# PCB_Breakout.net
KiCad netlist of a schematic drawn in EAGLE
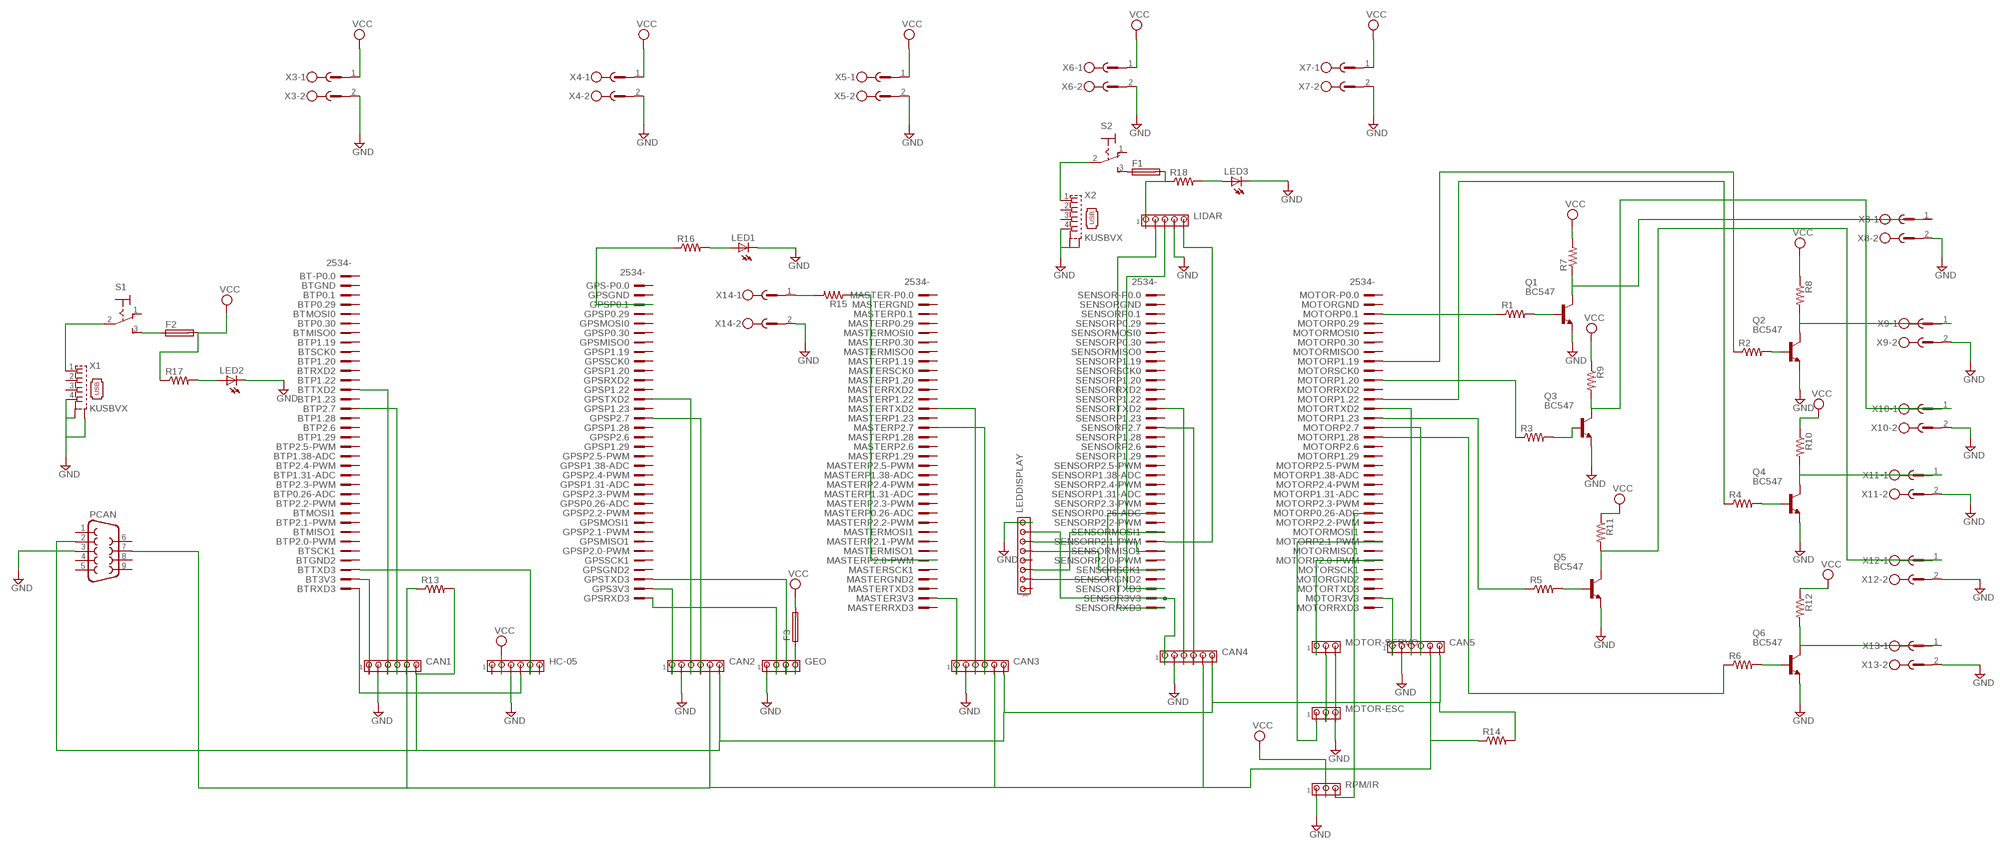
[diagram p0: schematic, sheet 1]

(export (version "E")
  (design (tool "Eeschema 10.0.6"))
  (components
    (comp (ref "BT")
      (value "2534-")
      (footprint "eagle-import:PAK100_2500-34")
      (libsource (lib "eagle-import") (part "2534-"))
    )
    (comp (ref "CAN1")
      (value "MTA06-100")
      (footprint "eagle-import:10X06MTA")
      (libsource (lib "eagle-import") (part "MTA06-100"))
    )
    (comp (ref "CAN2")
      (value "MTA06-100")
      (footprint "eagle-import:10X06MTA")
      (libsource (lib "eagle-import") (part "MTA06-100"))
    )
    (comp (ref "CAN3")
      (value "MTA06-100")
      (footprint "eagle-import:10X06MTA")
      (libsource (lib "eagle-import") (part "MTA06-100"))
    )
    (comp (ref "CAN4")
      (value "MTA06-100")
      (footprint "eagle-import:10X06MTA")
      (libsource (lib "eagle-import") (part "MTA06-100"))
    )
    (comp (ref "CAN5")
      (value "MTA06-100")
      (footprint "eagle-import:10X06MTA")
      (libsource (lib "eagle-import") (part "MTA06-100"))
    )
    (comp (ref "F1")
      (value "SH22,5")
      (footprint "eagle-import:SH22,5")
      (fields (field (name "MF") "SCHURTER") (field (name "MPN") "0031.8201"))
      (libsource (lib "eagle-import") (part "SH22,5"))
    )
    (comp (ref "F2")
      (value "SH22,5")
      (footprint "eagle-import:SH22,5")
      (fields (field (name "MF") "SCHURTER") (field (name "MPN") "0031.8201"))
      (libsource (lib "eagle-import") (part "SH22,5"))
    )
    (comp (ref "F3")
      (value "SH22,5")
      (footprint "eagle-import:SH22,5")
      (fields (field (name "MF") "SCHURTER") (field (name "MPN") "0031.8201"))
      (libsource (lib "eagle-import") (part "SH22,5"))
    )
    (comp (ref "GEO")
      (value "MTA04-100")
      (footprint "eagle-import:10X04MTA")
      (libsource (lib "eagle-import") (part "MTA04-100"))
    )
    (comp (ref "GPS")
      (value "2534-")
      (footprint "eagle-import:PAK100_2500-34")
      (libsource (lib "eagle-import") (part "2534-"))
    )
    (comp (ref "HC-05")
      (value "MTA06-100")
      (footprint "eagle-import:10X06MTA")
      (libsource (lib "eagle-import") (part "MTA06-100"))
    )
    (comp (ref "LED1")
      (value "LED5MM")
      (footprint "eagle-import:LED5MM")
      (libsource (lib "eagle-import") (part "LED5MM"))
    )
    (comp (ref "LED2")
      (value "LED5MM")
      (footprint "eagle-import:LED5MM")
      (libsource (lib "eagle-import") (part "LED5MM"))
    )
    (comp (ref "LED3")
      (value "LED5MM")
      (footprint "eagle-import:LED5MM")
      (libsource (lib "eagle-import") (part "LED5MM"))
    )
    (comp (ref "LEDDISPLAY")
      (value "MTA08-100")
      (footprint "eagle-import:10X08MTA")
      (libsource (lib "eagle-import") (part "MTA08-100"))
    )
    (comp (ref "LIDAR")
      (value "MTA05-100")
      (footprint "eagle-import:10X05MTA")
      (libsource (lib "eagle-import") (part "MTA05-100"))
    )
    (comp (ref "MASTER")
      (value "2534-")
      (footprint "eagle-import:PAK100_2500-34")
      (libsource (lib "eagle-import") (part "2534-"))
    )
    (comp (ref "MOTOR")
      (value "2534-")
      (footprint "eagle-import:PAK100_2500-34")
      (libsource (lib "eagle-import") (part "2534-"))
    )
    (comp (ref "MOTOR-ESC")
      (value "MTA03-100")
      (footprint "eagle-import:10X03MTA")
      (libsource (lib "eagle-import") (part "MTA03-100"))
    )
    (comp (ref "MOTOR-SERVO")
      (value "MTA03-100")
      (footprint "eagle-import:10X03MTA")
      (libsource (lib "eagle-import") (part "MTA03-100"))
    )
    (comp (ref "PCAN")
      (value "F09HP")
      (footprint "eagle-import:F09HP")
      (libsource (lib "eagle-import") (part "F09HP"))
    )
    (comp (ref "Q1")
      (value "BC547")
      (footprint "eagle-import:TO92")
      (libsource (lib "eagle-import") (part "BC547"))
    )
    (comp (ref "Q2")
      (value "BC547")
      (footprint "eagle-import:TO92")
      (libsource (lib "eagle-import") (part "BC547"))
    )
    (comp (ref "Q3")
      (value "BC547")
      (footprint "eagle-import:TO92")
      (libsource (lib "eagle-import") (part "BC547"))
    )
    (comp (ref "Q4")
      (value "BC547")
      (footprint "eagle-import:TO92")
      (libsource (lib "eagle-import") (part "BC547"))
    )
    (comp (ref "Q5")
      (value "BC547")
      (footprint "eagle-import:TO92")
      (libsource (lib "eagle-import") (part "BC547"))
    )
    (comp (ref "Q6")
      (value "BC547")
      (footprint "eagle-import:TO92")
      (libsource (lib "eagle-import") (part "BC547"))
    )
    (comp (ref "R1")
      (value "R-US_0207/10")
      (footprint "eagle-import:0207_10")
      (libsource (lib "eagle-import") (part "R-US_0207/10"))
    )
    (comp (ref "R2")
      (value "R-US_0207/10")
      (footprint "eagle-import:0207_10")
      (libsource (lib "eagle-import") (part "R-US_0207/10"))
    )
    (comp (ref "R3")
      (value "R-US_0207/10")
      (footprint "eagle-import:0207_10")
      (libsource (lib "eagle-import") (part "R-US_0207/10"))
    )
    (comp (ref "R4")
      (value "R-US_0207/10")
      (footprint "eagle-import:0207_10")
      (libsource (lib "eagle-import") (part "R-US_0207/10"))
    )
    (comp (ref "R5")
      (value "R-US_0207/10")
      (footprint "eagle-import:0207_10")
      (libsource (lib "eagle-import") (part "R-US_0207/10"))
    )
    (comp (ref "R6")
      (value "R-US_0207/10")
      (footprint "eagle-import:0207_10")
      (libsource (lib "eagle-import") (part "R-US_0207/10"))
    )
    (comp (ref "R7")
      (value "R-US_0207/10")
      (footprint "eagle-import:0207_10")
      (libsource (lib "eagle-import") (part "R-US_0207/10"))
    )
    (comp (ref "R8")
      (value "R-US_0207/10")
      (footprint "eagle-import:0207_10")
      (libsource (lib "eagle-import") (part "R-US_0207/10"))
    )
    (comp (ref "R9")
      (value "R-US_0207/10")
      (footprint "eagle-import:0207_10")
      (libsource (lib "eagle-import") (part "R-US_0207/10"))
    )
    (comp (ref "R10")
      (value "R-US_0207/10")
      (footprint "eagle-import:0207_10")
      (libsource (lib "eagle-import") (part "R-US_0207/10"))
    )
    (comp (ref "R11")
      (value "R-US_0207/10")
      (footprint "eagle-import:0207_10")
      (libsource (lib "eagle-import") (part "R-US_0207/10"))
    )
    (comp (ref "R12")
      (value "R-US_0207/10")
      (footprint "eagle-import:0207_10")
      (libsource (lib "eagle-import") (part "R-US_0207/10"))
    )
    (comp (ref "R13")
      (value "R-US_0207/10")
      (footprint "eagle-import:0207_10")
      (libsource (lib "eagle-import") (part "R-US_0207/10"))
    )
    (comp (ref "R14")
      (value "R-US_0207/10")
      (footprint "eagle-import:0207_10")
      (libsource (lib "eagle-import") (part "R-US_0207/10"))
    )
    (comp (ref "R15")
      (value "R-US_0207/10")
      (footprint "eagle-import:0207_10")
      (libsource (lib "eagle-import") (part "R-US_0207/10"))
    )
    (comp (ref "R16")
      (value "R-US_0207/10")
      (footprint "eagle-import:0207_10")
      (libsource (lib "eagle-import") (part "R-US_0207/10"))
    )
    (comp (ref "R17")
      (value "R-US_0207/10")
      (footprint "eagle-import:0207_10")
      (libsource (lib "eagle-import") (part "R-US_0207/10"))
    )
    (comp (ref "R18")
      (value "R-US_0207/10")
      (footprint "eagle-import:0207_10")
      (libsource (lib "eagle-import") (part "R-US_0207/10"))
    )
    (comp (ref "RPM/IR")
      (value "MTA03-100")
      (footprint "eagle-import:10X03MTA")
      (libsource (lib "eagle-import") (part "MTA03-100"))
    )
    (comp (ref "S1")
      (value "M9040P")
      (footprint "eagle-import:M9040P")
      (libsource (lib "eagle-import") (part "M9040P"))
    )
    (comp (ref "S2")
      (value "M9040P")
      (footprint "eagle-import:M9040P")
      (libsource (lib "eagle-import") (part "M9040P"))
    )
    (comp (ref "SENSOR")
      (value "2534-")
      (footprint "eagle-import:PAK100_2500-34")
      (libsource (lib "eagle-import") (part "2534-"))
    )
    (comp (ref "X1")
      (value "KUSBVX")
      (footprint "eagle-import:KUSBVX")
      (libsource (lib "eagle-import") (part "KUSBVX"))
    )
    (comp (ref "X2")
      (value "KUSBVX")
      (footprint "eagle-import:KUSBVX")
      (libsource (lib "eagle-import") (part "KUSBVX"))
    )
    (comp (ref "X3")
      (value "MSTBV2")
      (footprint "eagle-import:MSTBV2")
      (libsource (lib "eagle-import") (part "MSTBV2"))
    )
    (comp (ref "X4")
      (value "MSTBV2")
      (footprint "eagle-import:MSTBV2")
      (libsource (lib "eagle-import") (part "MSTBV2"))
    )
    (comp (ref "X5")
      (value "MSTBV2")
      (footprint "eagle-import:MSTBV2")
      (libsource (lib "eagle-import") (part "MSTBV2"))
    )
    (comp (ref "X6")
      (value "MSTBV2")
      (footprint "eagle-import:MSTBV2")
      (libsource (lib "eagle-import") (part "MSTBV2"))
    )
    (comp (ref "X7")
      (value "MSTBV2")
      (footprint "eagle-import:MSTBV2")
      (libsource (lib "eagle-import") (part "MSTBV2"))
    )
    (comp (ref "X8")
      (value "MSTBV2")
      (footprint "eagle-import:MSTBV2")
      (libsource (lib "eagle-import") (part "MSTBV2"))
    )
    (comp (ref "X9")
      (value "MSTBV2")
      (footprint "eagle-import:MSTBV2")
      (libsource (lib "eagle-import") (part "MSTBV2"))
    )
    (comp (ref "X10")
      (value "MSTBV2")
      (footprint "eagle-import:MSTBV2")
      (libsource (lib "eagle-import") (part "MSTBV2"))
    )
    (comp (ref "X11")
      (value "MSTBV2")
      (footprint "eagle-import:MSTBV2")
      (libsource (lib "eagle-import") (part "MSTBV2"))
    )
    (comp (ref "X12")
      (value "MSTBV2")
      (footprint "eagle-import:MSTBV2")
      (libsource (lib "eagle-import") (part "MSTBV2"))
    )
    (comp (ref "X13")
      (value "MSTBV2")
      (footprint "eagle-import:MSTBV2")
      (libsource (lib "eagle-import") (part "MSTBV2"))
    )
    (comp (ref "X14")
      (value "MSTBV2")
      (footprint "eagle-import:MSTBV2")
      (libsource (lib "eagle-import") (part "MSTBV2"))
    )
  )
  (nets
    (net (code "1") (name "GND") (class "Default")
      (node (ref "CAN1") (pin "5") (pinfunction "2_5") (pintype "passive"))
      (node (ref "CAN2") (pin "5") (pinfunction "2_5") (pintype "passive"))
      (node (ref "CAN3") (pin "5") (pinfunction "2_5") (pintype "passive"))
      (node (ref "CAN4") (pin "5") (pinfunction "2_5") (pintype "passive"))
      (node (ref "CAN5") (pin "5") (pinfunction "2_5") (pintype "passive"))
      (node (ref "GEO") (pin "1") (pinfunction "1_1") (pintype "passive"))
      (node (ref "HC-05") (pin "4") (pinfunction "3_4") (pintype "passive"))
      (node (ref "LED1") (pin "K") (pinfunction "C_K") (pintype "passive"))
      (node (ref "LED2") (pin "K") (pinfunction "C_K") (pintype "passive"))
      (node (ref "LED3") (pin "K") (pinfunction "C_K") (pintype "passive"))
      (node (ref "LEDDISPLAY") (pin "8") (pinfunction "8_8") (pintype "passive"))
      (node (ref "LIDAR") (pin "4") (pinfunction "4_4") (pintype "passive"))
      (node (ref "MOTOR-ESC") (pin "3") (pinfunction "3_3") (pintype "passive"))
      (node (ref "MOTOR-SERVO") (pin "3") (pinfunction "3_3") (pintype "passive"))
      (node (ref "PCAN") (pin "3") (pinfunction "3_3") (pintype "passive"))
      (node (ref "Q1") (pin "1") (pinfunction "E_1") (pintype "passive"))
      (node (ref "Q2") (pin "1") (pinfunction "E_1") (pintype "passive"))
      (node (ref "Q3") (pin "1") (pinfunction "E_1") (pintype "passive"))
      (node (ref "Q4") (pin "1") (pinfunction "E_1") (pintype "passive"))
      (node (ref "Q5") (pin "1") (pinfunction "E_1") (pintype "passive"))
      (node (ref "Q6") (pin "1") (pinfunction "E_1") (pintype "passive"))
      (node (ref "RPM/IR") (pin "1") (pinfunction "1_1") (pintype "passive"))
      (node (ref "X1") (pin "4") (pinfunction "4_4") (pintype "passive"))
      (node (ref "X1") (pin "M1") (pinfunction "S1_M1") (pintype "passive"))
      (node (ref "X1") (pin "M2") (pinfunction "S2_M2") (pintype "passive"))
      (node (ref "X10") (pin "2") (pinfunction "SK_2") (pintype "passive"))
      (node (ref "X11") (pin "2") (pinfunction "SK_2") (pintype "passive"))
      (node (ref "X12") (pin "2") (pinfunction "SK_2") (pintype "passive"))
      (node (ref "X13") (pin "2") (pinfunction "SK_2") (pintype "passive"))
      (node (ref "X14") (pin "2") (pinfunction "SK_2") (pintype "passive"))
      (node (ref "X2") (pin "4") (pinfunction "4_4") (pintype "passive"))
      (node (ref "X2") (pin "M1") (pinfunction "S1_M1") (pintype "passive"))
      (node (ref "X2") (pin "M2") (pinfunction "S2_M2") (pintype "passive"))
      (node (ref "X3") (pin "2") (pinfunction "SK_2") (pintype "passive"))
      (node (ref "X4") (pin "2") (pinfunction "SK_2") (pintype "passive"))
      (node (ref "X5") (pin "2") (pinfunction "SK_2") (pintype "passive"))
      (node (ref "X6") (pin "2") (pinfunction "SK_2") (pintype "passive"))
      (node (ref "X7") (pin "2") (pinfunction "SK_2") (pintype "passive"))
      (node (ref "X8") (pin "2") (pinfunction "SK_2") (pintype "passive"))
      (node (ref "X9") (pin "2") (pinfunction "SK_2") (pintype "passive"))
    )
    (net (code "2") (name "Net-(BTAB-KL)") (class "Default")
      (node (ref "BT") (pin "15") (pinfunction "KL_15") (pintype "passive"))
      (node (ref "CAN1") (pin "3") (pinfunction "4_3") (pintype "passive"))
    )
    (net (code "3") (name "Net-(BTAD-KL)") (class "Default")
      (node (ref "BT") (pin "34") (pinfunction "KL_34") (pintype "passive"))
      (node (ref "HC-05") (pin "3") (pinfunction "4_3") (pintype "passive"))
    )
    (net (code "4") (name "Net-(BTAG-KL)") (class "Default")
      (node (ref "BT") (pin "13") (pinfunction "KL_13") (pintype "passive"))
      (node (ref "CAN1") (pin "4") (pinfunction "3_4") (pintype "passive"))
    )
    (net (code "5") (name "Net-(BTAH-KL)") (class "Default")
      (node (ref "BT") (pin "32") (pinfunction "KL_32") (pintype "passive"))
      (node (ref "HC-05") (pin "2") (pinfunction "5_2") (pintype "passive"))
    )
    (net (code "6") (name "Net-(BTB-KL)") (class "Default")
      (node (ref "BT") (pin "33") (pinfunction "KL_33") (pintype "passive"))
      (node (ref "CAN1") (pin "6") (pinfunction "1_6") (pintype "passive"))
    )
    (net (code "7") (name "Net-(CAN1-5)") (class "Default")
      (node (ref "CAN1") (pin "2") (pinfunction "5_2") (pintype "passive"))
      (node (ref "CAN2") (pin "2") (pinfunction "5_2") (pintype "passive"))
      (node (ref "CAN3") (pin "2") (pinfunction "5_2") (pintype "passive"))
      (node (ref "CAN4") (pin "2") (pinfunction "5_2") (pintype "passive"))
      (node (ref "CAN5") (pin "2") (pinfunction "5_2") (pintype "passive"))
      (node (ref "PCAN") (pin "7") (pinfunction "7_7") (pintype "passive"))
      (node (ref "R13") (pin "1") (pinfunction "1_1") (pintype "passive"))
      (node (ref "R14") (pin "1") (pinfunction "1_1") (pintype "passive"))
    )
    (net (code "8") (name "Net-(CAN1-6)") (class "Default")
      (node (ref "CAN1") (pin "1") (pinfunction "6_1") (pintype "passive"))
      (node (ref "CAN2") (pin "1") (pinfunction "6_1") (pintype "passive"))
      (node (ref "CAN3") (pin "1") (pinfunction "6_1") (pintype "passive"))
      (node (ref "CAN4") (pin "1") (pinfunction "6_1") (pintype "passive"))
      (node (ref "CAN5") (pin "1") (pinfunction "6_1") (pintype "passive"))
      (node (ref "PCAN") (pin "2") (pinfunction "2_2") (pintype "passive"))
      (node (ref "R13") (pin "2") (pinfunction "2_2") (pintype "passive"))
      (node (ref "R14") (pin "2") (pinfunction "2_2") (pintype "passive"))
    )
    (net (code "9") (name "Net-(CAN2-1)") (class "Default")
      (node (ref "CAN2") (pin "6") (pinfunction "1_6") (pintype "passive"))
      (node (ref "GPS") (pin "33") (pinfunction "KL_33") (pintype "passive"))
    )
    (net (code "10") (name "Net-(CAN2-3)") (class "Default")
      (node (ref "CAN2") (pin "4") (pinfunction "3_4") (pintype "passive"))
      (node (ref "GPS") (pin "13") (pinfunction "KL_13") (pintype "passive"))
    )
    (net (code "11") (name "Net-(CAN2-4)") (class "Default")
      (node (ref "CAN2") (pin "3") (pinfunction "4_3") (pintype "passive"))
      (node (ref "GPS") (pin "15") (pinfunction "KL_15") (pintype "passive"))
    )
    (net (code "12") (name "Net-(CAN3-1)") (class "Default")
      (node (ref "CAN3") (pin "6") (pinfunction "1_6") (pintype "passive"))
      (node (ref "MASTER") (pin "33") (pinfunction "KL_33") (pintype "passive"))
    )
    (net (code "13") (name "Net-(CAN3-3)") (class "Default")
      (node (ref "CAN3") (pin "4") (pinfunction "3_4") (pintype "passive"))
      (node (ref "MASTER") (pin "13") (pinfunction "KL_13") (pintype "passive"))
    )
    (net (code "14") (name "Net-(CAN3-4)") (class "Default")
      (node (ref "CAN3") (pin "3") (pinfunction "4_3") (pintype "passive"))
      (node (ref "MASTER") (pin "15") (pinfunction "KL_15") (pintype "passive"))
    )
    (net (code "15") (name "Net-(CAN4-1)") (class "Default")
      (node (ref "CAN4") (pin "6") (pinfunction "1_6") (pintype "passive"))
      (node (ref "LEDDISPLAY") (pin "7") (pinfunction "7_7") (pintype "passive"))
      (node (ref "SENSOR") (pin "33") (pinfunction "KL_33") (pintype "passive"))
    )
    (net (code "16") (name "Net-(CAN4-3)") (class "Default")
      (node (ref "CAN4") (pin "4") (pinfunction "3_4") (pintype "passive"))
      (node (ref "SENSOR") (pin "13") (pinfunction "KL_13") (pintype "passive"))
    )
    (net (code "17") (name "Net-(CAN4-4)") (class "Default")
      (node (ref "CAN4") (pin "3") (pinfunction "4_3") (pintype "passive"))
      (node (ref "SENSOR") (pin "15") (pinfunction "KL_15") (pintype "passive"))
    )
    (net (code "18") (name "Net-(CAN5-1)") (class "Default")
      (node (ref "CAN5") (pin "6") (pinfunction "1_6") (pintype "passive"))
      (node (ref "MOTOR") (pin "33") (pinfunction "KL_33") (pintype "passive"))
    )
    (net (code "19") (name "Net-(CAN5-3)") (class "Default")
      (node (ref "CAN5") (pin "4") (pinfunction "3_4") (pintype "passive"))
      (node (ref "MOTOR") (pin "13") (pinfunction "KL_13") (pintype "passive"))
    )
    (net (code "20") (name "Net-(CAN5-4)") (class "Default")
      (node (ref "CAN5") (pin "3") (pinfunction "4_3") (pintype "passive"))
      (node (ref "MOTOR") (pin "15") (pinfunction "KL_15") (pintype "passive"))
    )
    (net (code "21") (name "Net-(F1-Pad2)") (class "Default")
      (node (ref "F1") (pin "2") (pinfunction "2_2") (pintype "passive"))
      (node (ref "LIDAR") (pin "1") (pinfunction "1_1") (pintype "passive"))
      (node (ref "R18") (pin "1") (pinfunction "1_1") (pintype "passive"))
    )
    (net (code "22") (name "Net-(F3-Pad1)") (class "Default")
      (node (ref "F3") (pin "1") (pinfunction "1_1") (pintype "passive"))
      (node (ref "GEO") (pin "4") (pinfunction "4_4") (pintype "passive"))
    )
    (net (code "23") (name "Net-(GPSAD-KL)") (class "Default")
      (node (ref "GEO") (pin "2") (pinfunction "2_2") (pintype "passive"))
      (node (ref "GPS") (pin "34") (pinfunction "KL_34") (pintype "passive"))
    )
    (net (code "24") (name "Net-(GPSAH-KL)") (class "Default")
      (node (ref "GEO") (pin "3") (pinfunction "3_3") (pintype "passive"))
      (node (ref "GPS") (pin "32") (pinfunction "KL_32") (pintype "passive"))
    )
    (net (code "25") (name "Net-(GPSI-KL)") (class "Default")
      (node (ref "GPS") (pin "3") (pinfunction "KL_3") (pintype "passive"))
      (node (ref "R16") (pin "1") (pinfunction "1_1") (pintype "passive"))
    )
    (net (code "26") (name "Net-(LED1-PadA)") (class "Default")
      (node (ref "LED1") (pin "A") (pinfunction "A_A") (pintype "passive"))
      (node (ref "R16") (pin "2") (pinfunction "2_2") (pintype "passive"))
    )
    (net (code "27") (name "Net-(LED2-PadA)") (class "Default")
      (node (ref "LED2") (pin "A") (pinfunction "A_A") (pintype "passive"))
      (node (ref "R17") (pin "2") (pinfunction "2_2") (pintype "passive"))
    )
    (net (code "28") (name "Net-(LED3-PadA)") (class "Default")
      (node (ref "LED3") (pin "A") (pinfunction "A_A") (pintype "passive"))
      (node (ref "R18") (pin "2") (pinfunction "2_2") (pintype "passive"))
    )
    (net (code "29") (name "Net-(MASTERU-KL)") (class "Default")
      (node (ref "MASTER") (pin "29") (pinfunction "KL_29") (pintype "passive"))
      (node (ref "R15") (pin "1") (pinfunction "1_1") (pintype "passive"))
    )
    (net (code "30") (name "Net-(MOTOR-ESC-Pad2)") (class "Default")
      (node (ref "MOTOR-ESC") (pin "2") (pinfunction "2_2") (pintype "passive"))
      (node (ref "MOTOR-SERVO") (pin "2") (pinfunction "2_2") (pintype "passive"))
    )
    (net (code "31") (name "Net-(MOTORI-KL)") (class "Default")
      (node (ref "MOTOR") (pin "3") (pinfunction "KL_3") (pintype "passive"))
      (node (ref "R1") (pin "1") (pinfunction "1_1") (pintype "passive"))
    )
    (net (code "32") (name "Net-(MOTORJ-KL)") (class "Default")
      (node (ref "MOTOR") (pin "24") (pinfunction "KL_24") (pintype "passive"))
      (node (ref "RPM/IR") (pin "3") (pinfunction "3_3") (pintype "passive"))
    )
    (net (code "33") (name "Net-(MOTORM-KL)") (class "Default")
      (node (ref "MOTOR") (pin "8") (pinfunction "KL_8") (pintype "passive"))
      (node (ref "R2") (pin "1") (pinfunction "1_1") (pintype "passive"))
    )
    (net (code "34") (name "Net-(MOTORN-KL)") (class "Default")
      (node (ref "MOTOR") (pin "10") (pinfunction "KL_10") (pintype "passive"))
      (node (ref "R3") (pin "1") (pinfunction "1_1") (pintype "passive"))
    )
    (net (code "35") (name "Net-(MOTORO-KL)") (class "Default")
      (node (ref "MOTOR") (pin "12") (pinfunction "KL_12") (pintype "passive"))
      (node (ref "R4") (pin "1") (pinfunction "1_1") (pintype "passive"))
    )
    (net (code "36") (name "Net-(MOTORP-KL)") (class "Default")
      (node (ref "MOTOR") (pin "14") (pinfunction "KL_14") (pintype "passive"))
      (node (ref "R5") (pin "1") (pinfunction "1_1") (pintype "passive"))
    )
    (net (code "37") (name "Net-(MOTORQ-KL)") (class "Default")
      (node (ref "MOTOR") (pin "16") (pinfunction "KL_16") (pintype "passive"))
      (node (ref "R6") (pin "1") (pinfunction "1_1") (pintype "passive"))
    )
    (net (code "38") (name "Net-(MOTORU-KL)") (class "Default")
      (node (ref "MOTOR") (pin "29") (pinfunction "KL_29") (pintype "passive"))
      (node (ref "MOTOR-SERVO") (pin "1") (pinfunction "1_1") (pintype "passive"))
    )
    (net (code "39") (name "Net-(MOTORV-KL)") (class "Default")
      (node (ref "MOTOR") (pin "27") (pinfunction "KL_27") (pintype "passive"))
      (node (ref "MOTOR-ESC") (pin "1") (pinfunction "1_1") (pintype "passive"))
    )
    (net (code "40") (name "Net-(Q1-B)") (class "Default")
      (node (ref "Q1") (pin "2") (pinfunction "B_2") (pintype "passive"))
      (node (ref "R1") (pin "2") (pinfunction "2_2") (pintype "passive"))
    )
    (net (code "41") (name "Net-(Q1-C)") (class "Default")
      (node (ref "Q1") (pin "3") (pinfunction "C_3") (pintype "passive"))
      (node (ref "R7") (pin "1") (pinfunction "1_1") (pintype "passive"))
      (node (ref "X8") (pin "1") (pinfunction "SK_1") (pintype "passive"))
    )
    (net (code "42") (name "Net-(Q2-B)") (class "Default")
      (node (ref "Q2") (pin "2") (pinfunction "B_2") (pintype "passive"))
      (node (ref "R2") (pin "2") (pinfunction "2_2") (pintype "passive"))
    )
    (net (code "43") (name "Net-(Q2-C)") (class "Default")
      (node (ref "Q2") (pin "3") (pinfunction "C_3") (pintype "passive"))
      (node (ref "R8") (pin "2") (pinfunction "2_2") (pintype "passive"))
      (node (ref "X9") (pin "1") (pinfunction "SK_1") (pintype "passive"))
    )
    (net (code "44") (name "Net-(Q3-B)") (class "Default")
      (node (ref "Q3") (pin "2") (pinfunction "B_2") (pintype "passive"))
      (node (ref "R3") (pin "2") (pinfunction "2_2") (pintype "passive"))
    )
    (net (code "45") (name "Net-(Q3-C)") (class "Default")
      (node (ref "Q3") (pin "3") (pinfunction "C_3") (pintype "passive"))
      (node (ref "R9") (pin "2") (pinfunction "2_2") (pintype "passive"))
      (node (ref "X10") (pin "1") (pinfunction "SK_1") (pintype "passive"))
    )
    (net (code "46") (name "Net-(Q4-B)") (class "Default")
      (node (ref "Q4") (pin "2") (pinfunction "B_2") (pintype "passive"))
      (node (ref "R4") (pin "2") (pinfunction "2_2") (pintype "passive"))
    )
    (net (code "47") (name "Net-(Q4-C)") (class "Default")
      (node (ref "Q4") (pin "3") (pinfunction "C_3") (pintype "passive"))
      (node (ref "R10") (pin "2") (pinfunction "2_2") (pintype "passive"))
      (node (ref "X11") (pin "1") (pinfunction "SK_1") (pintype "passive"))
    )
    (net (code "48") (name "Net-(Q5-B)") (class "Default")
      (node (ref "Q5") (pin "2") (pinfunction "B_2") (pintype "passive"))
      (node (ref "R5") (pin "2") (pinfunction "2_2") (pintype "passive"))
    )
    (net (code "49") (name "Net-(Q5-C)") (class "Default")
      (node (ref "Q5") (pin "3") (pinfunction "C_3") (pintype "passive"))
      (node (ref "R11") (pin "2") (pinfunction "2_2") (pintype "passive"))
      (node (ref "X12") (pin "1") (pinfunction "SK_1") (pintype "passive"))
    )
    (net (code "50") (name "Net-(Q6-B)") (class "Default")
      (node (ref "Q6") (pin "2") (pinfunction "B_2") (pintype "passive"))
      (node (ref "R6") (pin "2") (pinfunction "2_2") (pintype "passive"))
    )
    (net (code "51") (name "Net-(Q6-C)") (class "Default")
      (node (ref "Q6") (pin "3") (pinfunction "C_3") (pintype "passive"))
      (node (ref "R12") (pin "2") (pinfunction "2_2") (pintype "passive"))
      (node (ref "X13") (pin "1") (pinfunction "SK_1") (pintype "passive"))
    )
    (net (code "52") (name "Net-(S1-P)") (class "Default")
      (node (ref "S1") (pin "2") (pinfunction "P_2") (pintype "passive"))
      (node (ref "X1") (pin "1") (pinfunction "1_1") (pintype "passive"))
    )
    (net (code "53") (name "Net-(S1-S)") (class "Default")
      (node (ref "F2") (pin "1") (pinfunction "1_1") (pintype "passive"))
      (node (ref "S1") (pin "3") (pinfunction "S_3") (pintype "passive"))
    )
    (net (code "54") (name "Net-(S2-P)") (class "Default")
      (node (ref "S2") (pin "2") (pinfunction "P_2") (pintype "passive"))
      (node (ref "X2") (pin "1") (pinfunction "1_1") (pintype "passive"))
    )
    (net (code "55") (name "Net-(S2-S)") (class "Default")
      (node (ref "F1") (pin "1") (pinfunction "1_1") (pintype "passive"))
      (node (ref "S2") (pin "3") (pinfunction "S_3") (pintype "passive"))
    )
    (net (code "56") (name "Net-(SENSORAD-KL)") (class "Default")
      (node (ref "LIDAR") (pin "2") (pinfunction "2_2") (pintype "passive"))
      (node (ref "SENSOR") (pin "34") (pinfunction "KL_34") (pintype "passive"))
    )
    (net (code "57") (name "Net-(SENSORAF-KL)") (class "Default")
      (node (ref "LEDDISPLAY") (pin "5") (pinfunction "5_5") (pintype "passive"))
      (node (ref "SENSOR") (pin "30") (pinfunction "KL_30") (pintype "passive"))
    )
    (net (code "58") (name "Net-(SENSORAH-KL)") (class "Default")
      (node (ref "LIDAR") (pin "3") (pinfunction "3_3") (pintype "passive"))
      (node (ref "SENSOR") (pin "32") (pinfunction "KL_32") (pintype "passive"))
    )
    (net (code "59") (name "Net-(SENSORF-KL)") (class "Default")
      (node (ref "LEDDISPLAY") (pin "6") (pinfunction "6_6") (pintype "passive"))
      (node (ref "SENSOR") (pin "28") (pinfunction "KL_28") (pintype "passive"))
    )
    (net (code "60") (name "Net-(SENSORH-KL)") (class "Default")
      (node (ref "LEDDISPLAY") (pin "3") (pinfunction "3_3") (pintype "passive"))
      (node (ref "SENSOR") (pin "26") (pinfunction "KL_26") (pintype "passive"))
    )
    (net (code "61") (name "Net-(SENSORJ-KL)") (class "Default")
      (node (ref "LEDDISPLAY") (pin "2") (pinfunction "2_2") (pintype "passive"))
      (node (ref "SENSOR") (pin "24") (pinfunction "KL_24") (pintype "passive"))
    )
    (net (code "62") (name "Net-(SENSORV-KL)") (class "Default")
      (node (ref "LIDAR") (pin "5") (pinfunction "5_5") (pintype "passive"))
      (node (ref "SENSOR") (pin "27") (pinfunction "KL_27") (pintype "passive"))
    )
    (net (code "63") (name "Net-(X14A-SK)") (class "Default")
      (node (ref "R15") (pin "2") (pinfunction "2_2") (pintype "passive"))
      (node (ref "X14") (pin "1") (pinfunction "SK_1") (pintype "passive"))
    )
    (net (code "64") (name "VCC") (class "Default")
      (node (ref "F2") (pin "2") (pinfunction "2_2") (pintype "passive"))
      (node (ref "F3") (pin "2") (pinfunction "2_2") (pintype "passive"))
      (node (ref "HC-05") (pin "5") (pinfunction "2_5") (pintype "passive"))
      (node (ref "R10") (pin "1") (pinfunction "1_1") (pintype "passive"))
      (node (ref "R11") (pin "1") (pinfunction "1_1") (pintype "passive"))
      (node (ref "R12") (pin "1") (pinfunction "1_1") (pintype "passive"))
      (node (ref "R17") (pin "1") (pinfunction "1_1") (pintype "passive"))
      (node (ref "R7") (pin "2") (pinfunction "2_2") (pintype "passive"))
      (node (ref "R8") (pin "1") (pinfunction "1_1") (pintype "passive"))
      (node (ref "R9") (pin "1") (pinfunction "1_1") (pintype "passive"))
      (node (ref "RPM/IR") (pin "2") (pinfunction "2_2") (pintype "passive"))
      (node (ref "X3") (pin "1") (pinfunction "SK_1") (pintype "passive"))
      (node (ref "X4") (pin "1") (pinfunction "SK_1") (pintype "passive"))
      (node (ref "X5") (pin "1") (pinfunction "SK_1") (pintype "passive"))
      (node (ref "X6") (pin "1") (pinfunction "SK_1") (pintype "passive"))
      (node (ref "X7") (pin "1") (pinfunction "SK_1") (pintype "passive"))
    )
    (net (code "65") (name "unconnected-(BTA-KL-Pad1)") (class "Default")
      (node (ref "BT") (pin "1") (pinfunction "KL_1") (pintype "passive"))
    )
    (net (code "66") (name "unconnected-(BTAA-KL-Pad17)") (class "Default")
      (node (ref "BT") (pin "17") (pinfunction "KL_17") (pintype "passive"))
    )
    (net (code "67") (name "unconnected-(BTAC-KL-Pad11)") (class "Default")
      (node (ref "BT") (pin "11") (pinfunction "KL_11") (pintype "passive"))
    )
    (net (code "68") (name "unconnected-(BTAE-KL-Pad9)") (class "Default")
      (node (ref "BT") (pin "9") (pinfunction "KL_9") (pintype "passive"))
    )
    (net (code "69") (name "unconnected-(BTAF-KL-Pad30)") (class "Default")
      (node (ref "BT") (pin "30") (pinfunction "KL_30") (pintype "passive"))
    )
    (net (code "70") (name "unconnected-(BTC-KL-Pad2)") (class "Default")
      (node (ref "BT") (pin "2") (pinfunction "KL_2") (pintype "passive"))
    )
    (net (code "71") (name "unconnected-(BTD-KL-Pad31)") (class "Default")
      (node (ref "BT") (pin "31") (pinfunction "KL_31") (pintype "passive"))
    )
    (net (code "72") (name "unconnected-(BTE-KL-Pad7)") (class "Default")
      (node (ref "BT") (pin "7") (pinfunction "KL_7") (pintype "passive"))
    )
    (net (code "73") (name "unconnected-(BTF-KL-Pad28)") (class "Default")
      (node (ref "BT") (pin "28") (pinfunction "KL_28") (pintype "passive"))
    )
    (net (code "74") (name "unconnected-(BTG-KL-Pad5)") (class "Default")
      (node (ref "BT") (pin "5") (pinfunction "KL_5") (pintype "passive"))
    )
    (net (code "75") (name "unconnected-(BTH-KL-Pad26)") (class "Default")
      (node (ref "BT") (pin "26") (pinfunction "KL_26") (pintype "passive"))
    )
    (net (code "76") (name "unconnected-(BTI-KL-Pad3)") (class "Default")
      (node (ref "BT") (pin "3") (pinfunction "KL_3") (pintype "passive"))
    )
    (net (code "77") (name "unconnected-(BTJ-KL-Pad24)") (class "Default")
      (node (ref "BT") (pin "24") (pinfunction "KL_24") (pintype "passive"))
    )
    (net (code "78") (name "unconnected-(BTK-KL-Pad4)") (class "Default")
      (node (ref "BT") (pin "4") (pinfunction "KL_4") (pintype "passive"))
    )
    (net (code "79") (name "unconnected-(BTL-KL-Pad6)") (class "Default")
      (node (ref "BT") (pin "6") (pinfunction "KL_6") (pintype "passive"))
    )
    (net (code "80") (name "unconnected-(BTM-KL-Pad8)") (class "Default")
      (node (ref "BT") (pin "8") (pinfunction "KL_8") (pintype "passive"))
    )
    (net (code "81") (name "unconnected-(BTN-KL-Pad10)") (class "Default")
      (node (ref "BT") (pin "10") (pinfunction "KL_10") (pintype "passive"))
    )
    (net (code "82") (name "unconnected-(BTO-KL-Pad12)") (class "Default")
      (node (ref "BT") (pin "12") (pinfunction "KL_12") (pintype "passive"))
    )
    (net (code "83") (name "unconnected-(BTP-KL-Pad14)") (class "Default")
      (node (ref "BT") (pin "14") (pinfunction "KL_14") (pintype "passive"))
    )
    (net (code "84") (name "unconnected-(BTQ-KL-Pad16)") (class "Default")
      (node (ref "BT") (pin "16") (pinfunction "KL_16") (pintype "passive"))
    )
    (net (code "85") (name "unconnected-(BTR-KL-Pad18)") (class "Default")
      (node (ref "BT") (pin "18") (pinfunction "KL_18") (pintype "passive"))
    )
    (net (code "86") (name "unconnected-(BTS-KL-Pad22)") (class "Default")
      (node (ref "BT") (pin "22") (pinfunction "KL_22") (pintype "passive"))
    )
    (net (code "87") (name "unconnected-(BTT-KL-Pad20)") (class "Default")
      (node (ref "BT") (pin "20") (pinfunction "KL_20") (pintype "passive"))
    )
    (net (code "88") (name "unconnected-(BTU-KL-Pad29)") (class "Default")
      (node (ref "BT") (pin "29") (pinfunction "KL_29") (pintype "passive"))
    )
    (net (code "89") (name "unconnected-(BTV-KL-Pad27)") (class "Default")
      (node (ref "BT") (pin "27") (pinfunction "KL_27") (pintype "passive"))
    )
    (net (code "90") (name "unconnected-(BTW-KL-Pad25)") (class "Default")
      (node (ref "BT") (pin "25") (pinfunction "KL_25") (pintype "passive"))
    )
    (net (code "91") (name "unconnected-(BTX-KL-Pad23)") (class "Default")
      (node (ref "BT") (pin "23") (pinfunction "KL_23") (pintype "passive"))
    )
    (net (code "92") (name "unconnected-(BTY-KL-Pad21)") (class "Default")
      (node (ref "BT") (pin "21") (pinfunction "KL_21") (pintype "passive"))
    )
    (net (code "93") (name "unconnected-(BTZ-KL-Pad19)") (class "Default")
      (node (ref "BT") (pin "19") (pinfunction "KL_19") (pintype "passive"))
    )
    (net (code "94") (name "unconnected-(GPSA-KL-Pad1)") (class "Default")
      (node (ref "GPS") (pin "1") (pinfunction "KL_1") (pintype "passive"))
    )
    (net (code "95") (name "unconnected-(GPSAA-KL-Pad17)") (class "Default")
      (node (ref "GPS") (pin "17") (pinfunction "KL_17") (pintype "passive"))
    )
    (net (code "96") (name "unconnected-(GPSAC-KL-Pad11)") (class "Default")
      (node (ref "GPS") (pin "11") (pinfunction "KL_11") (pintype "passive"))
    )
    (net (code "97") (name "unconnected-(GPSAE-KL-Pad9)") (class "Default")
      (node (ref "GPS") (pin "9") (pinfunction "KL_9") (pintype "passive"))
    )
    (net (code "98") (name "unconnected-(GPSAF-KL-Pad30)") (class "Default")
      (node (ref "GPS") (pin "30") (pinfunction "KL_30") (pintype "passive"))
    )
    (net (code "99") (name "unconnected-(GPSC-KL-Pad2)") (class "Default")
      (node (ref "GPS") (pin "2") (pinfunction "KL_2") (pintype "passive"))
    )
    (net (code "100") (name "unconnected-(GPSD-KL-Pad31)") (class "Default")
      (node (ref "GPS") (pin "31") (pinfunction "KL_31") (pintype "passive"))
    )
    (net (code "101") (name "unconnected-(GPSE-KL-Pad7)") (class "Default")
      (node (ref "GPS") (pin "7") (pinfunction "KL_7") (pintype "passive"))
    )
    (net (code "102") (name "unconnected-(GPSF-KL-Pad28)") (class "Default")
      (node (ref "GPS") (pin "28") (pinfunction "KL_28") (pintype "passive"))
    )
    (net (code "103") (name "unconnected-(GPSG-KL-Pad5)") (class "Default")
      (node (ref "GPS") (pin "5") (pinfunction "KL_5") (pintype "passive"))
    )
    (net (code "104") (name "unconnected-(GPSH-KL-Pad26)") (class "Default")
      (node (ref "GPS") (pin "26") (pinfunction "KL_26") (pintype "passive"))
    )
    (net (code "105") (name "unconnected-(GPSJ-KL-Pad24)") (class "Default")
      (node (ref "GPS") (pin "24") (pinfunction "KL_24") (pintype "passive"))
    )
    (net (code "106") (name "unconnected-(GPSK-KL-Pad4)") (class "Default")
      (node (ref "GPS") (pin "4") (pinfunction "KL_4") (pintype "passive"))
    )
    (net (code "107") (name "unconnected-(GPSL-KL-Pad6)") (class "Default")
      (node (ref "GPS") (pin "6") (pinfunction "KL_6") (pintype "passive"))
    )
    (net (code "108") (name "unconnected-(GPSM-KL-Pad8)") (class "Default")
      (node (ref "GPS") (pin "8") (pinfunction "KL_8") (pintype "passive"))
    )
    (net (code "109") (name "unconnected-(GPSN-KL-Pad10)") (class "Default")
      (node (ref "GPS") (pin "10") (pinfunction "KL_10") (pintype "passive"))
    )
    (net (code "110") (name "unconnected-(GPSO-KL-Pad12)") (class "Default")
      (node (ref "GPS") (pin "12") (pinfunction "KL_12") (pintype "passive"))
    )
    (net (code "111") (name "unconnected-(GPSP-KL-Pad14)") (class "Default")
      (node (ref "GPS") (pin "14") (pinfunction "KL_14") (pintype "passive"))
    )
    (net (code "112") (name "unconnected-(GPSQ-KL-Pad16)") (class "Default")
      (node (ref "GPS") (pin "16") (pinfunction "KL_16") (pintype "passive"))
    )
    (net (code "113") (name "unconnected-(GPSR-KL-Pad18)") (class "Default")
      (node (ref "GPS") (pin "18") (pinfunction "KL_18") (pintype "passive"))
    )
    (net (code "114") (name "unconnected-(GPSS-KL-Pad22)") (class "Default")
      (node (ref "GPS") (pin "22") (pinfunction "KL_22") (pintype "passive"))
    )
    (net (code "115") (name "unconnected-(GPST-KL-Pad20)") (class "Default")
      (node (ref "GPS") (pin "20") (pinfunction "KL_20") (pintype "passive"))
    )
    (net (code "116") (name "unconnected-(GPSU-KL-Pad29)") (class "Default")
      (node (ref "GPS") (pin "29") (pinfunction "KL_29") (pintype "passive"))
    )
    (net (code "117") (name "unconnected-(GPSV-KL-Pad27)") (class "Default")
      (node (ref "GPS") (pin "27") (pinfunction "KL_27") (pintype "passive"))
    )
    (net (code "118") (name "unconnected-(GPSW-KL-Pad25)") (class "Default")
      (node (ref "GPS") (pin "25") (pinfunction "KL_25") (pintype "passive"))
    )
    (net (code "119") (name "unconnected-(GPSX-KL-Pad23)") (class "Default")
      (node (ref "GPS") (pin "23") (pinfunction "KL_23") (pintype "passive"))
    )
    (net (code "120") (name "unconnected-(GPSY-KL-Pad21)") (class "Default")
      (node (ref "GPS") (pin "21") (pinfunction "KL_21") (pintype "passive"))
    )
    (net (code "121") (name "unconnected-(GPSZ-KL-Pad19)") (class "Default")
      (node (ref "GPS") (pin "19") (pinfunction "KL_19") (pintype "passive"))
    )
    (net (code "122") (name "unconnected-(HC-05-1-Pad6)") (class "Default")
      (node (ref "HC-05") (pin "6") (pinfunction "1_6") (pintype "passive"))
    )
    (net (code "123") (name "unconnected-(HC-05-6-Pad1)") (class "Default")
      (node (ref "HC-05") (pin "1") (pinfunction "6_1") (pintype "passive"))
    )
    (net (code "124") (name "unconnected-(LEDDISPLAY-Pad1)") (class "Default")
      (node (ref "LEDDISPLAY") (pin "1") (pinfunction "1_1") (pintype "passive"))
    )
    (net (code "125") (name "unconnected-(LEDDISPLAY-Pad4)") (class "Default")
      (node (ref "LEDDISPLAY") (pin "4") (pinfunction "4_4") (pintype "passive"))
    )
    (net (code "126") (name "unconnected-(MASTERA-KL-Pad1)") (class "Default")
      (node (ref "MASTER") (pin "1") (pinfunction "KL_1") (pintype "passive"))
    )
    (net (code "127") (name "unconnected-(MASTERAA-KL-Pad17)") (class "Default")
      (node (ref "MASTER") (pin "17") (pinfunction "KL_17") (pintype "passive"))
    )
    (net (code "128") (name "unconnected-(MASTERAC-KL-Pad11)") (class "Default")
      (node (ref "MASTER") (pin "11") (pinfunction "KL_11") (pintype "passive"))
    )
    (net (code "129") (name "unconnected-(MASTERAD-KL-Pad34)") (class "Default")
      (node (ref "MASTER") (pin "34") (pinfunction "KL_34") (pintype "passive"))
    )
    (net (code "130") (name "unconnected-(MASTERAE-KL-Pad9)") (class "Default")
      (node (ref "MASTER") (pin "9") (pinfunction "KL_9") (pintype "passive"))
    )
    (net (code "131") (name "unconnected-(MASTERAF-KL-Pad30)") (class "Default")
      (node (ref "MASTER") (pin "30") (pinfunction "KL_30") (pintype "passive"))
    )
    (net (code "132") (name "unconnected-(MASTERAH-KL-Pad32)") (class "Default")
      (node (ref "MASTER") (pin "32") (pinfunction "KL_32") (pintype "passive"))
    )
    (net (code "133") (name "unconnected-(MASTERC-KL-Pad2)") (class "Default")
      (node (ref "MASTER") (pin "2") (pinfunction "KL_2") (pintype "passive"))
    )
    (net (code "134") (name "unconnected-(MASTERD-KL-Pad31)") (class "Default")
      (node (ref "MASTER") (pin "31") (pinfunction "KL_31") (pintype "passive"))
    )
    (net (code "135") (name "unconnected-(MASTERE-KL-Pad7)") (class "Default")
      (node (ref "MASTER") (pin "7") (pinfunction "KL_7") (pintype "passive"))
    )
    (net (code "136") (name "unconnected-(MASTERF-KL-Pad28)") (class "Default")
      (node (ref "MASTER") (pin "28") (pinfunction "KL_28") (pintype "passive"))
    )
    (net (code "137") (name "unconnected-(MASTERG-KL-Pad5)") (class "Default")
      (node (ref "MASTER") (pin "5") (pinfunction "KL_5") (pintype "passive"))
    )
    (net (code "138") (name "unconnected-(MASTERH-KL-Pad26)") (class "Default")
      (node (ref "MASTER") (pin "26") (pinfunction "KL_26") (pintype "passive"))
    )
    (net (code "139") (name "unconnected-(MASTERI-KL-Pad3)") (class "Default")
      (node (ref "MASTER") (pin "3") (pinfunction "KL_3") (pintype "passive"))
    )
    (net (code "140") (name "unconnected-(MASTERJ-KL-Pad24)") (class "Default")
      (node (ref "MASTER") (pin "24") (pinfunction "KL_24") (pintype "passive"))
    )
    (net (code "141") (name "unconnected-(MASTERK-KL-Pad4)") (class "Default")
      (node (ref "MASTER") (pin "4") (pinfunction "KL_4") (pintype "passive"))
    )
    (net (code "142") (name "unconnected-(MASTERL-KL-Pad6)") (class "Default")
      (node (ref "MASTER") (pin "6") (pinfunction "KL_6") (pintype "passive"))
    )
    (net (code "143") (name "unconnected-(MASTERM-KL-Pad8)") (class "Default")
      (node (ref "MASTER") (pin "8") (pinfunction "KL_8") (pintype "passive"))
    )
    (net (code "144") (name "unconnected-(MASTERN-KL-Pad10)") (class "Default")
      (node (ref "MASTER") (pin "10") (pinfunction "KL_10") (pintype "passive"))
    )
    (net (code "145") (name "unconnected-(MASTERO-KL-Pad12)") (class "Default")
      (node (ref "MASTER") (pin "12") (pinfunction "KL_12") (pintype "passive"))
    )
    (net (code "146") (name "unconnected-(MASTERP-KL-Pad14)") (class "Default")
      (node (ref "MASTER") (pin "14") (pinfunction "KL_14") (pintype "passive"))
    )
    (net (code "147") (name "unconnected-(MASTERQ-KL-Pad16)") (class "Default")
      (node (ref "MASTER") (pin "16") (pinfunction "KL_16") (pintype "passive"))
    )
    (net (code "148") (name "unconnected-(MASTERR-KL-Pad18)") (class "Default")
      (node (ref "MASTER") (pin "18") (pinfunction "KL_18") (pintype "passive"))
    )
    (net (code "149") (name "unconnected-(MASTERS-KL-Pad22)") (class "Default")
      (node (ref "MASTER") (pin "22") (pinfunction "KL_22") (pintype "passive"))
    )
    (net (code "150") (name "unconnected-(MASTERT-KL-Pad20)") (class "Default")
      (node (ref "MASTER") (pin "20") (pinfunction "KL_20") (pintype "passive"))
    )
    (net (code "151") (name "unconnected-(MASTERV-KL-Pad27)") (class "Default")
      (node (ref "MASTER") (pin "27") (pinfunction "KL_27") (pintype "passive"))
    )
    (net (code "152") (name "unconnected-(MASTERW-KL-Pad25)") (class "Default")
      (node (ref "MASTER") (pin "25") (pinfunction "KL_25") (pintype "passive"))
    )
    (net (code "153") (name "unconnected-(MASTERX-KL-Pad23)") (class "Default")
      (node (ref "MASTER") (pin "23") (pinfunction "KL_23") (pintype "passive"))
    )
    (net (code "154") (name "unconnected-(MASTERY-KL-Pad21)") (class "Default")
      (node (ref "MASTER") (pin "21") (pinfunction "KL_21") (pintype "passive"))
    )
    (net (code "155") (name "unconnected-(MASTERZ-KL-Pad19)") (class "Default")
      (node (ref "MASTER") (pin "19") (pinfunction "KL_19") (pintype "passive"))
    )
    (net (code "156") (name "unconnected-(MOTORA-KL-Pad1)") (class "Default")
      (node (ref "MOTOR") (pin "1") (pinfunction "KL_1") (pintype "passive"))
    )
    (net (code "157") (name "unconnected-(MOTORAA-KL-Pad17)") (class "Default")
      (node (ref "MOTOR") (pin "17") (pinfunction "KL_17") (pintype "passive"))
    )
    (net (code "158") (name "unconnected-(MOTORAC-KL-Pad11)") (class "Default")
      (node (ref "MOTOR") (pin "11") (pinfunction "KL_11") (pintype "passive"))
    )
    (net (code "159") (name "unconnected-(MOTORAD-KL-Pad34)") (class "Default")
      (node (ref "MOTOR") (pin "34") (pinfunction "KL_34") (pintype "passive"))
    )
    (net (code "160") (name "unconnected-(MOTORAE-KL-Pad9)") (class "Default")
      (node (ref "MOTOR") (pin "9") (pinfunction "KL_9") (pintype "passive"))
    )
    (net (code "161") (name "unconnected-(MOTORAF-KL-Pad30)") (class "Default")
      (node (ref "MOTOR") (pin "30") (pinfunction "KL_30") (pintype "passive"))
    )
    (net (code "162") (name "unconnected-(MOTORAH-KL-Pad32)") (class "Default")
      (node (ref "MOTOR") (pin "32") (pinfunction "KL_32") (pintype "passive"))
    )
    (net (code "163") (name "unconnected-(MOTORC-KL-Pad2)") (class "Default")
      (node (ref "MOTOR") (pin "2") (pinfunction "KL_2") (pintype "passive"))
    )
    (net (code "164") (name "unconnected-(MOTORD-KL-Pad31)") (class "Default")
      (node (ref "MOTOR") (pin "31") (pinfunction "KL_31") (pintype "passive"))
    )
    (net (code "165") (name "unconnected-(MOTORE-KL-Pad7)") (class "Default")
      (node (ref "MOTOR") (pin "7") (pinfunction "KL_7") (pintype "passive"))
    )
    (net (code "166") (name "unconnected-(MOTORF-KL-Pad28)") (class "Default")
      (node (ref "MOTOR") (pin "28") (pinfunction "KL_28") (pintype "passive"))
    )
    (net (code "167") (name "unconnected-(MOTORG-KL-Pad5)") (class "Default")
      (node (ref "MOTOR") (pin "5") (pinfunction "KL_5") (pintype "passive"))
    )
    (net (code "168") (name "unconnected-(MOTORH-KL-Pad26)") (class "Default")
      (node (ref "MOTOR") (pin "26") (pinfunction "KL_26") (pintype "passive"))
    )
    (net (code "169") (name "unconnected-(MOTORK-KL-Pad4)") (class "Default")
      (node (ref "MOTOR") (pin "4") (pinfunction "KL_4") (pintype "passive"))
    )
    (net (code "170") (name "unconnected-(MOTORL-KL-Pad6)") (class "Default")
      (node (ref "MOTOR") (pin "6") (pinfunction "KL_6") (pintype "passive"))
    )
    (net (code "171") (name "unconnected-(MOTORR-KL-Pad18)") (class "Default")
      (node (ref "MOTOR") (pin "18") (pinfunction "KL_18") (pintype "passive"))
    )
    (net (code "172") (name "unconnected-(MOTORS-KL-Pad22)") (class "Default")
      (node (ref "MOTOR") (pin "22") (pinfunction "KL_22") (pintype "passive"))
    )
    (net (code "173") (name "unconnected-(MOTORT-KL-Pad20)") (class "Default")
      (node (ref "MOTOR") (pin "20") (pinfunction "KL_20") (pintype "passive"))
    )
    (net (code "174") (name "unconnected-(MOTORW-KL-Pad25)") (class "Default")
      (node (ref "MOTOR") (pin "25") (pinfunction "KL_25") (pintype "passive"))
    )
    (net (code "175") (name "unconnected-(MOTORX-KL-Pad23)") (class "Default")
      (node (ref "MOTOR") (pin "23") (pinfunction "KL_23") (pintype "passive"))
    )
    (net (code "176") (name "unconnected-(MOTORY-KL-Pad21)") (class "Default")
      (node (ref "MOTOR") (pin "21") (pinfunction "KL_21") (pintype "passive"))
    )
    (net (code "177") (name "unconnected-(MOTORZ-KL-Pad19)") (class "Default")
      (node (ref "MOTOR") (pin "19") (pinfunction "KL_19") (pintype "passive"))
    )
    (net (code "178") (name "unconnected-(PCAN-Pad1)") (class "Default")
      (node (ref "PCAN") (pin "1") (pinfunction "1_1") (pintype "passive"))
    )
    (net (code "179") (name "unconnected-(PCAN-Pad4)") (class "Default")
      (node (ref "PCAN") (pin "4") (pinfunction "4_4") (pintype "passive"))
    )
    (net (code "180") (name "unconnected-(PCAN-Pad5)") (class "Default")
      (node (ref "PCAN") (pin "5") (pinfunction "5_5") (pintype "passive"))
    )
    (net (code "181") (name "unconnected-(PCAN-Pad6)") (class "Default")
      (node (ref "PCAN") (pin "6") (pinfunction "6_6") (pintype "passive"))
    )
    (net (code "182") (name "unconnected-(PCAN-Pad8)") (class "Default")
      (node (ref "PCAN") (pin "8") (pinfunction "8_8") (pintype "passive"))
    )
    (net (code "183") (name "unconnected-(PCAN-Pad9)") (class "Default")
      (node (ref "PCAN") (pin "9") (pinfunction "9_9") (pintype "passive"))
    )
    (net (code "184") (name "unconnected-(S1-O-Pad1)") (class "Default")
      (node (ref "S1") (pin "1") (pinfunction "O_1") (pintype "passive"))
    )
    (net (code "185") (name "unconnected-(S2-O-Pad1)") (class "Default")
      (node (ref "S2") (pin "1") (pinfunction "O_1") (pintype "passive"))
    )
    (net (code "186") (name "unconnected-(SENSORA-KL-Pad1)") (class "Default")
      (node (ref "SENSOR") (pin "1") (pinfunction "KL_1") (pintype "passive"))
    )
    (net (code "187") (name "unconnected-(SENSORAA-KL-Pad17)") (class "Default")
      (node (ref "SENSOR") (pin "17") (pinfunction "KL_17") (pintype "passive"))
    )
    (net (code "188") (name "unconnected-(SENSORAC-KL-Pad11)") (class "Default")
      (node (ref "SENSOR") (pin "11") (pinfunction "KL_11") (pintype "passive"))
    )
    (net (code "189") (name "unconnected-(SENSORAE-KL-Pad9)") (class "Default")
      (node (ref "SENSOR") (pin "9") (pinfunction "KL_9") (pintype "passive"))
    )
    (net (code "190") (name "unconnected-(SENSORC-KL-Pad2)") (class "Default")
      (node (ref "SENSOR") (pin "2") (pinfunction "KL_2") (pintype "passive"))
    )
    (net (code "191") (name "unconnected-(SENSORD-KL-Pad31)") (class "Default")
      (node (ref "SENSOR") (pin "31") (pinfunction "KL_31") (pintype "passive"))
    )
    (net (code "192") (name "unconnected-(SENSORE-KL-Pad7)") (class "Default")
      (node (ref "SENSOR") (pin "7") (pinfunction "KL_7") (pintype "passive"))
    )
    (net (code "193") (name "unconnected-(SENSORG-KL-Pad5)") (class "Default")
      (node (ref "SENSOR") (pin "5") (pinfunction "KL_5") (pintype "passive"))
    )
    (net (code "194") (name "unconnected-(SENSORI-KL-Pad3)") (class "Default")
      (node (ref "SENSOR") (pin "3") (pinfunction "KL_3") (pintype "passive"))
    )
    (net (code "195") (name "unconnected-(SENSORK-KL-Pad4)") (class "Default")
      (node (ref "SENSOR") (pin "4") (pinfunction "KL_4") (pintype "passive"))
    )
    (net (code "196") (name "unconnected-(SENSORL-KL-Pad6)") (class "Default")
      (node (ref "SENSOR") (pin "6") (pinfunction "KL_6") (pintype "passive"))
    )
    (net (code "197") (name "unconnected-(SENSORM-KL-Pad8)") (class "Default")
      (node (ref "SENSOR") (pin "8") (pinfunction "KL_8") (pintype "passive"))
    )
    (net (code "198") (name "unconnected-(SENSORN-KL-Pad10)") (class "Default")
      (node (ref "SENSOR") (pin "10") (pinfunction "KL_10") (pintype "passive"))
    )
    (net (code "199") (name "unconnected-(SENSORO-KL-Pad12)") (class "Default")
      (node (ref "SENSOR") (pin "12") (pinfunction "KL_12") (pintype "passive"))
    )
    (net (code "200") (name "unconnected-(SENSORP-KL-Pad14)") (class "Default")
      (node (ref "SENSOR") (pin "14") (pinfunction "KL_14") (pintype "passive"))
    )
    (net (code "201") (name "unconnected-(SENSORQ-KL-Pad16)") (class "Default")
      (node (ref "SENSOR") (pin "16") (pinfunction "KL_16") (pintype "passive"))
    )
    (net (code "202") (name "unconnected-(SENSORR-KL-Pad18)") (class "Default")
      (node (ref "SENSOR") (pin "18") (pinfunction "KL_18") (pintype "passive"))
    )
    (net (code "203") (name "unconnected-(SENSORS-KL-Pad22)") (class "Default")
      (node (ref "SENSOR") (pin "22") (pinfunction "KL_22") (pintype "passive"))
    )
    (net (code "204") (name "unconnected-(SENSORT-KL-Pad20)") (class "Default")
      (node (ref "SENSOR") (pin "20") (pinfunction "KL_20") (pintype "passive"))
    )
    (net (code "205") (name "unconnected-(SENSORU-KL-Pad29)") (class "Default")
      (node (ref "SENSOR") (pin "29") (pinfunction "KL_29") (pintype "passive"))
    )
    (net (code "206") (name "unconnected-(SENSORW-KL-Pad25)") (class "Default")
      (node (ref "SENSOR") (pin "25") (pinfunction "KL_25") (pintype "passive"))
    )
    (net (code "207") (name "unconnected-(SENSORX-KL-Pad23)") (class "Default")
      (node (ref "SENSOR") (pin "23") (pinfunction "KL_23") (pintype "passive"))
    )
    (net (code "208") (name "unconnected-(SENSORY-KL-Pad21)") (class "Default")
      (node (ref "SENSOR") (pin "21") (pinfunction "KL_21") (pintype "passive"))
    )
    (net (code "209") (name "unconnected-(SENSORZ-KL-Pad19)") (class "Default")
      (node (ref "SENSOR") (pin "19") (pinfunction "KL_19") (pintype "passive"))
    )
    (net (code "210") (name "unconnected-(X1-Pad2)") (class "Default")
      (node (ref "X1") (pin "2") (pinfunction "2_2") (pintype "passive"))
    )
    (net (code "211") (name "unconnected-(X1-Pad3)") (class "Default")
      (node (ref "X1") (pin "3") (pinfunction "3_3") (pintype "passive"))
    )
    (net (code "212") (name "unconnected-(X2-Pad2)") (class "Default")
      (node (ref "X2") (pin "2") (pinfunction "2_2") (pintype "passive"))
    )
    (net (code "213") (name "unconnected-(X2-Pad3)") (class "Default")
      (node (ref "X2") (pin "3") (pinfunction "3_3") (pintype "passive"))
    )
  )
)
